# STM3205P_CurrentMeasure.net
KiCad netlist of a schematic drawn in Altium Designer
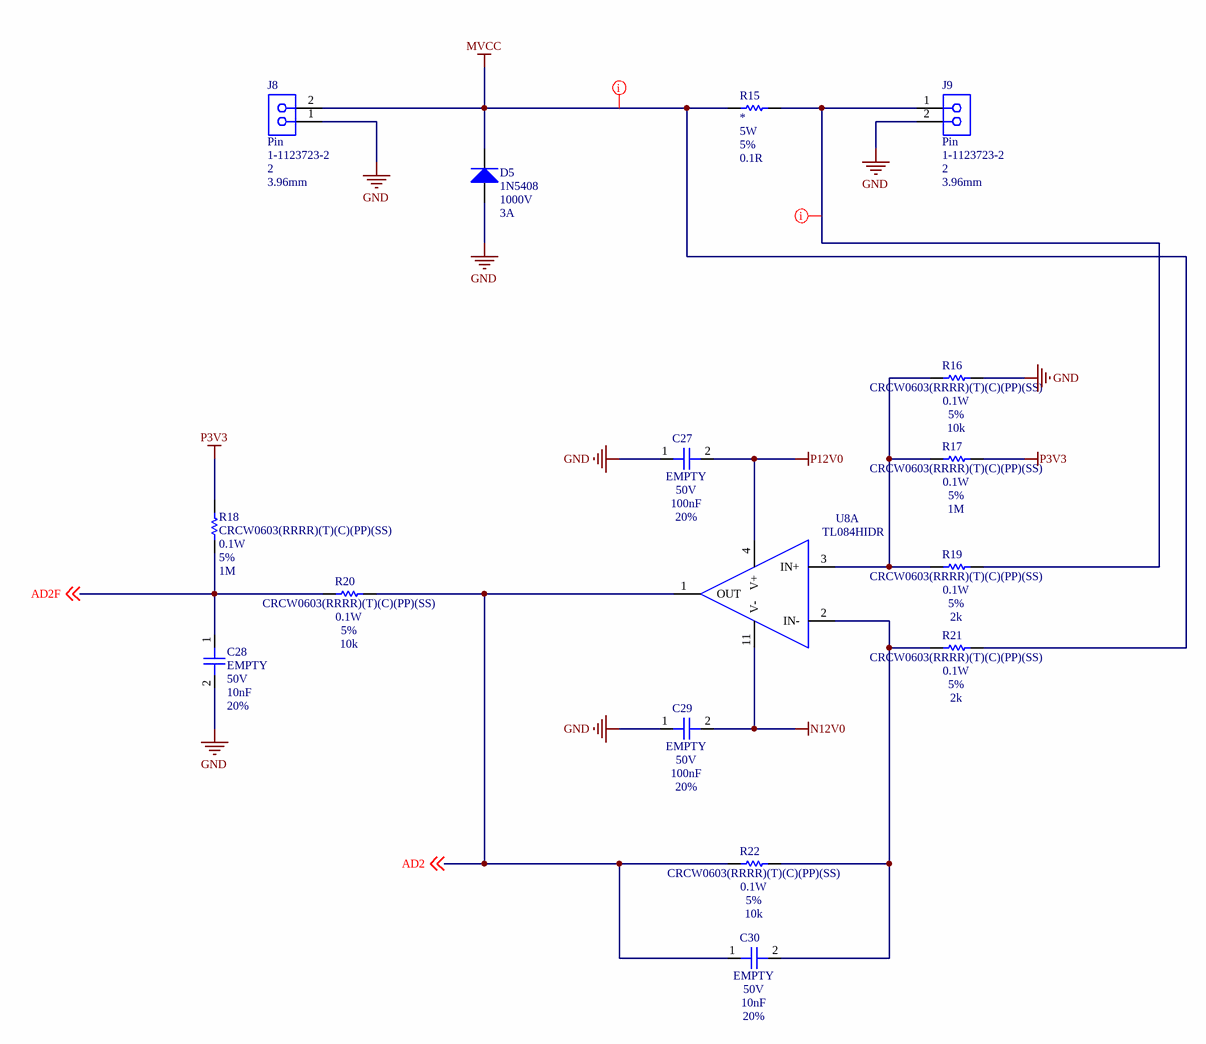
[diagram p0: STM3205P_CurrentMeasure.SchDoc]

(export (version "E")
  (design (tool "Eeschema 10.0.6"))
  (components
    (comp (ref "C27")
      (value "100nF")
      (footprint "CAP0603")
      (description "Surface Mount Multilayer Ceramic Chip Capacitors  for Commercial Applications")
      (fields
        (field (name "PARTNUMBER1") "EMPTY")
        (field (name "VOLTAGE") "50V")
        (field (name "TOLERANCE") "20%")
        (field (name "Comment") "CC0603")
        (field (name "PUBLISHER") "Lucas Moraes")
      )
      (libsource (lib "CeramicCapacitors") (part "CC0603"))
    )
    (comp (ref "C28")
      (value "10nF")
      (footprint "CAP0603")
      (description "Surface Mount Multilayer Ceramic Chip Capacitors  for Commercial Applications")
      (fields
        (field (name "PARTNUMBER1") "EMPTY")
        (field (name "VOLTAGE") "50V")
        (field (name "TOLERANCE") "20%")
        (field (name "Comment") "CC0603")
        (field (name "PUBLISHER") "Lucas Moraes")
      )
      (libsource (lib "CeramicCapacitors") (part "CC0603"))
    )
    (comp (ref "C29")
      (value "100nF")
      (footprint "CAP0603")
      (description "Surface Mount Multilayer Ceramic Chip Capacitors  for Commercial Applications")
      (fields
        (field (name "PARTNUMBER1") "EMPTY")
        (field (name "VOLTAGE") "50V")
        (field (name "TOLERANCE") "20%")
        (field (name "Comment") "CC0603")
        (field (name "PUBLISHER") "Lucas Moraes")
      )
      (libsource (lib "CeramicCapacitors") (part "CC0603"))
    )
    (comp (ref "C30")
      (value "10nF")
      (footprint "CAP0603")
      (description "Surface Mount Multilayer Ceramic Chip Capacitors  for Commercial Applications")
      (fields
        (field (name "PARTNUMBER1") "EMPTY")
        (field (name "VOLTAGE") "50V")
        (field (name "TOLERANCE") "20%")
        (field (name "Comment") "CC0603")
        (field (name "PUBLISHER") "Lucas Moraes")
      )
      (libsource (lib "CeramicCapacitors") (part "CC0603"))
    )
    (comp (ref "D5")
      (value "1N5408")
      (footprint "DO-201AD")
      (description "Rectifiers Diode, 1000V, 3A")
      (fields
        (field (name "PARTNUMBER1") "1N5408")
        (field (name "VRRM") "1000V")
        (field (name "IF") "3A")
        (field (name "PUBLISHER") "Lucas Moraes")
      )
      (libsource (lib "RectifierDiode") (part "1N5408"))
    )
    (comp (ref "J8")
      (value "1-1123723-2")
      (footprint "CONKK02STRMALE_156")
      (description "Header Vert 3.96mm 2Pos")
      (fields
        (field (name "TYPE") "Pin")
        (field (name "PARTNUMBER1") "1-1123723-2")
        (field (name "PINS") "2")
        (field (name "PITCH") "3.96mm")
        (field (name "PUBLISHER") "Lucas Moraes")
      )
      (libsource (lib "HeaderPin") (part "1-1123723-2"))
    )
    (comp (ref "J9")
      (value "1-1123723-2")
      (footprint "CONKK02STRMALE_156")
      (description "Header Vert 3.96mm 2Pos")
      (fields
        (field (name "TYPE") "Pin")
        (field (name "PARTNUMBER1") "1-1123723-2")
        (field (name "PINS") "2")
        (field (name "PITCH") "3.96mm")
        (field (name "PUBLISHER") "Lucas Moraes")
      )
      (libsource (lib "HeaderPin") (part "1-1123723-2"))
    )
    (comp (ref "R15")
      (value "0.1R")
      (footprint "RESSHUNT")
      (description "Thick Film Chip Resistors with CECC Approval,  available with Established Reliability")
      (fields
        (field (name "PARTNUMBER1") "*")
        (field (name "POWER") "5W")
        (field (name "TOLERANCE") "5%")
        (field (name "Comment") "Chip Resistor")
        (field (name "PUBLISHER") "Lucas Moraes")
      )
      (libsource (lib "STM3205P_SpecialLib") (part "RESSHUNT"))
    )
    (comp (ref "R16")
      (value "10k")
      (footprint "RES0603")
      (description "Thick Film Chip Resistors with CECC Approval,  available with Established Reliability")
      (fields
        (field (name "PARTNUMBER1") "CRCW0603(RRRR)(T)(C)(PP)(SS)")
        (field (name "POWER") "0.1W")
        (field (name "TOLERANCE") "5%")
        (field (name "Comment") "Chip Resistor")
        (field (name "PUBLISHER") "Lucas Moraes")
      )
      (libsource (lib "ResistorsFixed") (part "CRCW0603"))
    )
    (comp (ref "R17")
      (value "1M")
      (footprint "RES0603")
      (description "Thick Film Chip Resistors with CECC Approval,  available with Established Reliability")
      (fields
        (field (name "PARTNUMBER1") "CRCW0603(RRRR)(T)(C)(PP)(SS)")
        (field (name "POWER") "0.1W")
        (field (name "TOLERANCE") "5%")
        (field (name "Comment") "Chip Resistor")
        (field (name "PUBLISHER") "Lucas Moraes")
      )
      (libsource (lib "ResistorsFixed") (part "CRCW0603"))
    )
    (comp (ref "R18")
      (value "1M")
      (footprint "RES0603")
      (description "Thick Film Chip Resistors with CECC Approval,  available with Established Reliability")
      (fields
        (field (name "PARTNUMBER1") "CRCW0603(RRRR)(T)(C)(PP)(SS)")
        (field (name "POWER") "0.1W")
        (field (name "TOLERANCE") "5%")
        (field (name "Comment") "Chip Resistor")
        (field (name "PUBLISHER") "Lucas Moraes")
      )
      (libsource (lib "ResistorsFixed") (part "CRCW0603"))
    )
    (comp (ref "R19")
      (value "2k")
      (footprint "RES0603")
      (description "Thick Film Chip Resistors with CECC Approval,  available with Established Reliability")
      (fields
        (field (name "PARTNUMBER1") "CRCW0603(RRRR)(T)(C)(PP)(SS)")
        (field (name "POWER") "0.1W")
        (field (name "TOLERANCE") "5%")
        (field (name "Comment") "Chip Resistor")
        (field (name "PUBLISHER") "Lucas Moraes")
      )
      (libsource (lib "ResistorsFixed") (part "CRCW0603"))
    )
    (comp (ref "R20")
      (value "10k")
      (footprint "RES0603")
      (description "Thick Film Chip Resistors with CECC Approval,  available with Established Reliability")
      (fields
        (field (name "PARTNUMBER1") "CRCW0603(RRRR)(T)(C)(PP)(SS)")
        (field (name "POWER") "0.1W")
        (field (name "TOLERANCE") "5%")
        (field (name "Comment") "Chip Resistor")
        (field (name "PUBLISHER") "Lucas Moraes")
      )
      (libsource (lib "ResistorsFixed") (part "CRCW0603"))
    )
    (comp (ref "R21")
      (value "2k")
      (footprint "RES0603")
      (description "Thick Film Chip Resistors with CECC Approval,  available with Established Reliability")
      (fields
        (field (name "PARTNUMBER1") "CRCW0603(RRRR)(T)(C)(PP)(SS)")
        (field (name "POWER") "0.1W")
        (field (name "TOLERANCE") "5%")
        (field (name "Comment") "Chip Resistor")
        (field (name "PUBLISHER") "Lucas Moraes")
      )
      (libsource (lib "ResistorsFixed") (part "CRCW0603"))
    )
    (comp (ref "R22")
      (value "10k")
      (footprint "RES0603")
      (description "Thick Film Chip Resistors with CECC Approval,  available with Established Reliability")
      (fields
        (field (name "PARTNUMBER1") "CRCW0603(RRRR)(T)(C)(PP)(SS)")
        (field (name "POWER") "0.1W")
        (field (name "TOLERANCE") "5%")
        (field (name "Comment") "Chip Resistor")
        (field (name "PUBLISHER") "Lucas Moraes")
      )
      (libsource (lib "ResistorsFixed") (part "CRCW0603"))
    )
    (comp (ref "U8")
      (value "TL084HIDR")
      (footprint "SOIC-14-3.9mm")
      (description "Quad Operational Amplifiers RRIO")
      (fields (field (name "PARTNUMBER1") "TL084HIDR") (field (name "PUBLISHER") "Lucas Moraes"))
      (libsource (lib "Amplifiers") (part "TL084HIDR"))
    )
  )
  (nets
    (net (code "1") (name "AD2") (class "Default")
      (node (ref "C30") (pin "1") (pinfunction "1_1") (pintype "passive"))
      (node (ref "R20") (pin "2") (pinfunction "2_2") (pintype "passive"))
      (node (ref "R22") (pin "1") (pinfunction "1_1") (pintype "passive"))
      (node (ref "U8") (pin "1") (pinfunction "OUT_1") (pintype "passive"))
    )
    (net (code "2") (name "AD2F") (class "Default")
      (node (ref "C28") (pin "1") (pinfunction "1_1") (pintype "passive"))
      (node (ref "R18") (pin "1") (pinfunction "1_1") (pintype "passive"))
      (node (ref "R20") (pin "1") (pinfunction "1_1") (pintype "passive"))
    )
    (net (code "3") (name "GND") (class "Default")
      (node (ref "C27") (pin "1") (pinfunction "1_1") (pintype "passive"))
      (node (ref "C28") (pin "2") (pinfunction "2_2") (pintype "passive"))
      (node (ref "C29") (pin "1") (pinfunction "1_1") (pintype "passive"))
      (node (ref "D5") (pin "A") (pinfunction "A_A") (pintype "passive"))
      (node (ref "J8") (pin "1") (pinfunction "1_1") (pintype "passive"))
      (node (ref "J9") (pin "2") (pinfunction "2_2") (pintype "passive"))
      (node (ref "R16") (pin "2") (pinfunction "2_2") (pintype "passive"))
    )
    (net (code "4") (name "MVCC") (class "Default")
      (node (ref "D5") (pin "K") (pinfunction "K_K") (pintype "passive"))
      (node (ref "J8") (pin "2") (pinfunction "2_2") (pintype "passive"))
      (node (ref "R15") (pin "2") (pinfunction "2_2") (pintype "passive"))
      (node (ref "R21") (pin "2") (pinfunction "2_2") (pintype "passive"))
    )
    (net (code "5") (name "N12V0") (class "Default")
      (node (ref "C29") (pin "2") (pinfunction "2_2") (pintype "passive"))
      (node (ref "U8") (pin "11") (pinfunction "V-_11") (pintype "passive"))
    )
    (net (code "6") (name "Net-(J9-Pad1)") (class "Default")
      (node (ref "J9") (pin "1") (pinfunction "1_1") (pintype "passive"))
      (node (ref "R15") (pin "1") (pinfunction "1_1") (pintype "passive"))
      (node (ref "R19") (pin "2") (pinfunction "2_2") (pintype "passive"))
    )
    (net (code "7") (name "Net-(U8A-IN+)") (class "Default")
      (node (ref "R16") (pin "1") (pinfunction "1_1") (pintype "passive"))
      (node (ref "R17") (pin "1") (pinfunction "1_1") (pintype "passive"))
      (node (ref "R19") (pin "1") (pinfunction "1_1") (pintype "passive"))
      (node (ref "U8") (pin "3") (pinfunction "IN+_3") (pintype "passive"))
    )
    (net (code "8") (name "Net-(U8A-IN-)") (class "Default")
      (node (ref "C30") (pin "2") (pinfunction "2_2") (pintype "passive"))
      (node (ref "R21") (pin "1") (pinfunction "1_1") (pintype "passive"))
      (node (ref "R22") (pin "2") (pinfunction "2_2") (pintype "passive"))
      (node (ref "U8") (pin "2") (pinfunction "IN-_2") (pintype "passive"))
    )
    (net (code "9") (name "P3V3") (class "Default")
      (node (ref "R17") (pin "2") (pinfunction "2_2") (pintype "passive"))
      (node (ref "R18") (pin "2") (pinfunction "2_2") (pintype "passive"))
    )
    (net (code "10") (name "P12V0") (class "Default")
      (node (ref "C27") (pin "2") (pinfunction "2_2") (pintype "passive"))
      (node (ref "U8") (pin "4") (pinfunction "V+_4") (pintype "passive"))
    )
  )
)
